# Active_Bandpass_Filter_reference_power.net
KiCad netlist of a schematic drawn in EAGLE
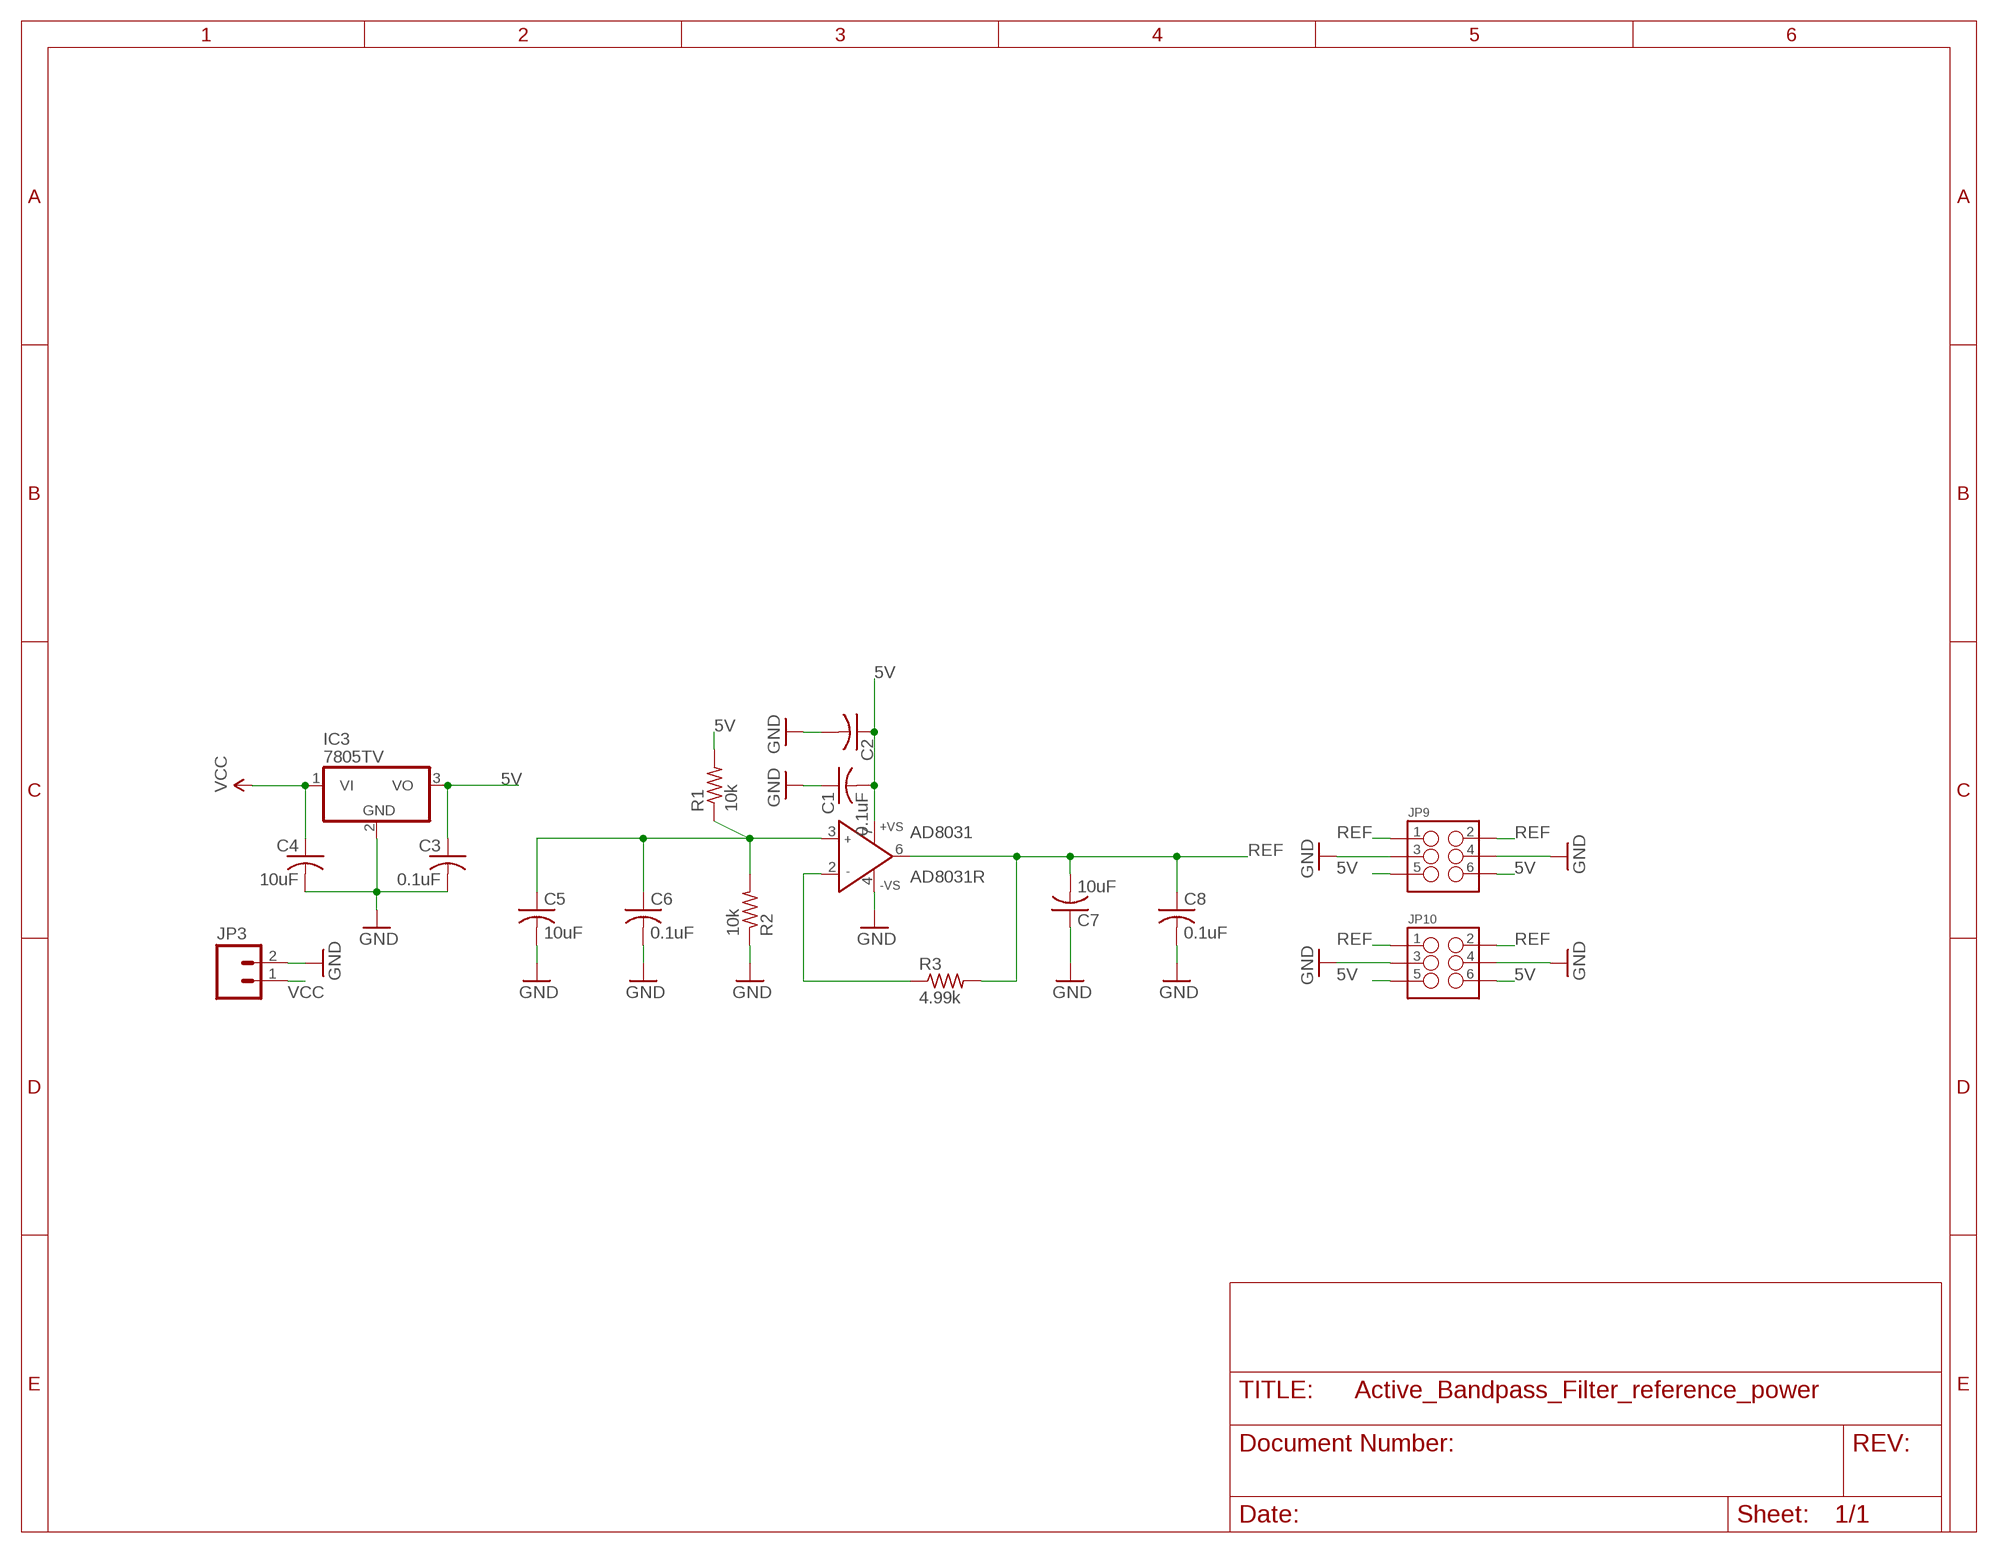
[diagram p0: schematic, sheet 1]

(export (version "E")
  (design (tool "Eeschema 10.0.6"))
  (components
    (comp (ref "AD8031")
      (value "AD8031R")
      (footprint "eagle-import:SO8")
      (fields (field (name "MPN") "AD8031ARZ"))
      (libsource (lib "eagle-import") (part "AD8031R"))
    )
    (comp (ref "C1")
      (value "0.1uF")
      (footprint "eagle-import:C1206")
      (libsource (lib "eagle-import") (part "C-USC1206"))
    )
    (comp (ref "C2")
      (value "C-USC1206")
      (footprint "eagle-import:C1206")
      (libsource (lib "eagle-import") (part "C-USC1206"))
    )
    (comp (ref "C3")
      (value "0.1uF")
      (footprint "eagle-import:C1206")
      (libsource (lib "eagle-import") (part "C-USC1206"))
    )
    (comp (ref "C4")
      (value "10uF")
      (footprint "eagle-import:C1206")
      (libsource (lib "eagle-import") (part "C-USC1206"))
    )
    (comp (ref "C5")
      (value "10uF")
      (footprint "eagle-import:C1206")
      (libsource (lib "eagle-import") (part "C-USC1206"))
    )
    (comp (ref "C6")
      (value "0.1uF")
      (footprint "eagle-import:C1206")
      (libsource (lib "eagle-import") (part "C-USC1206"))
    )
    (comp (ref "C7")
      (value "10uF")
      (footprint "eagle-import:C1206")
      (libsource (lib "eagle-import") (part "C-USC1206"))
    )
    (comp (ref "C8")
      (value "0.1uF")
      (footprint "eagle-import:C1206")
      (libsource (lib "eagle-import") (part "C-USC1206"))
    )
    (comp (ref "IC3")
      (value "7805TV")
      (footprint "eagle-import:TO220V")
      (libsource (lib "eagle-import") (part "78TV05"))
    )
    (comp (ref "JP3")
      (value "M02LOCK_LONGPADS")
      (footprint "eagle-import:1X02_LOCK_LONGPADS")
      (libsource (lib "eagle-import") (part "M02LOCK_LONGPADS"))
    )
    (comp (ref "JP9")
      (value "M03X22X3_SILK_MALE_PTH")
      (footprint "eagle-import:2X3")
      (libsource (lib "eagle-import") (part "M03X22X3_SILK_MALE_PTH"))
    )
    (comp (ref "JP10")
      (value "M03X22X3_SILK_MALE_PTH")
      (footprint "eagle-import:2X3")
      (libsource (lib "eagle-import") (part "M03X22X3_SILK_MALE_PTH"))
    )
    (comp (ref "R1")
      (value "10k")
      (footprint "eagle-import:R1206")
      (libsource (lib "eagle-import") (part "resistor_R-US_R1206"))
    )
    (comp (ref "R2")
      (value "10k")
      (footprint "eagle-import:R1206")
      (libsource (lib "eagle-import") (part "resistor_R-US_R1206"))
    )
    (comp (ref "R3")
      (value "4.99k")
      (footprint "eagle-import:R1206")
      (libsource (lib "eagle-import") (part "R-US_R1206"))
    )
  )
  (nets
    (net (code "1") (name "/5V") (class "Default")
      (node (ref "AD8031") (pin "7") (pinfunction "+VS_7") (pintype "input"))
      (node (ref "C1") (pin "2") (pinfunction "2_2") (pintype "passive"))
      (node (ref "C2") (pin "1") (pinfunction "1_1") (pintype "passive"))
      (node (ref "C3") (pin "1") (pinfunction "1_1") (pintype "passive"))
      (node (ref "IC3") (pin "3") (pinfunction "VO_3") (pintype "passive"))
      (node (ref "JP10") (pin "5") (pinfunction "5_5") (pintype "bidirectional"))
      (node (ref "JP10") (pin "6") (pinfunction "6_6") (pintype "bidirectional"))
      (node (ref "JP9") (pin "5") (pinfunction "5_5") (pintype "bidirectional"))
      (node (ref "JP9") (pin "6") (pinfunction "6_6") (pintype "bidirectional"))
      (node (ref "R1") (pin "2") (pinfunction "2_2") (pintype "passive"))
    )
    (net (code "2") (name "/REF") (class "Default")
      (node (ref "AD8031") (pin "6") (pinfunction "OUT_6") (pintype "output"))
      (node (ref "C7") (pin "2") (pinfunction "2_2") (pintype "passive"))
      (node (ref "C8") (pin "1") (pinfunction "1_1") (pintype "passive"))
      (node (ref "JP10") (pin "1") (pinfunction "1_1") (pintype "bidirectional"))
      (node (ref "JP10") (pin "2") (pinfunction "2_2") (pintype "bidirectional"))
      (node (ref "JP9") (pin "1") (pinfunction "1_1") (pintype "bidirectional"))
      (node (ref "JP9") (pin "2") (pinfunction "2_2") (pintype "bidirectional"))
      (node (ref "R3") (pin "2") (pinfunction "2_2") (pintype "passive"))
    )
    (net (code "3") (name "GND") (class "Default")
      (node (ref "AD8031") (pin "4") (pinfunction "-VS_4") (pintype "input"))
      (node (ref "C1") (pin "1") (pinfunction "1_1") (pintype "passive"))
      (node (ref "C2") (pin "2") (pinfunction "2_2") (pintype "passive"))
      (node (ref "C3") (pin "2") (pinfunction "2_2") (pintype "passive"))
      (node (ref "C4") (pin "2") (pinfunction "2_2") (pintype "passive"))
      (node (ref "C5") (pin "2") (pinfunction "2_2") (pintype "passive"))
      (node (ref "C6") (pin "2") (pinfunction "2_2") (pintype "passive"))
      (node (ref "C7") (pin "1") (pinfunction "1_1") (pintype "passive"))
      (node (ref "C8") (pin "2") (pinfunction "2_2") (pintype "passive"))
      (node (ref "IC3") (pin "2") (pinfunction "GND_2") (pintype "passive"))
      (node (ref "JP10") (pin "3") (pinfunction "3_3") (pintype "bidirectional"))
      (node (ref "JP10") (pin "4") (pinfunction "4_4") (pintype "bidirectional"))
      (node (ref "JP3") (pin "2") (pinfunction "2_2") (pintype "passive"))
      (node (ref "JP9") (pin "3") (pinfunction "3_3") (pintype "bidirectional"))
      (node (ref "JP9") (pin "4") (pinfunction "4_4") (pintype "bidirectional"))
      (node (ref "R2") (pin "1") (pinfunction "1_1") (pintype "passive"))
    )
    (net (code "4") (name "Net-(AD8031-IN+)") (class "Default")
      (node (ref "AD8031") (pin "3") (pinfunction "IN+_3") (pintype "input"))
      (node (ref "C5") (pin "1") (pinfunction "1_1") (pintype "passive"))
      (node (ref "C6") (pin "1") (pinfunction "1_1") (pintype "passive"))
      (node (ref "R1") (pin "1") (pinfunction "1_1") (pintype "passive"))
      (node (ref "R2") (pin "2") (pinfunction "2_2") (pintype "passive"))
    )
    (net (code "5") (name "Net-(AD8031-IN-)") (class "Default")
      (node (ref "AD8031") (pin "2") (pinfunction "IN-_2") (pintype "input"))
      (node (ref "R3") (pin "1") (pinfunction "1_1") (pintype "passive"))
    )
    (net (code "6") (name "VCC") (class "Default")
      (node (ref "C4") (pin "1") (pinfunction "1_1") (pintype "passive"))
      (node (ref "IC3") (pin "1") (pinfunction "VI_1") (pintype "input"))
      (node (ref "JP3") (pin "1") (pinfunction "1_1") (pintype "passive"))
    )
  )
)
